# smogbuster-v2.net
KiCad netlist of a schematic drawn in EAGLE
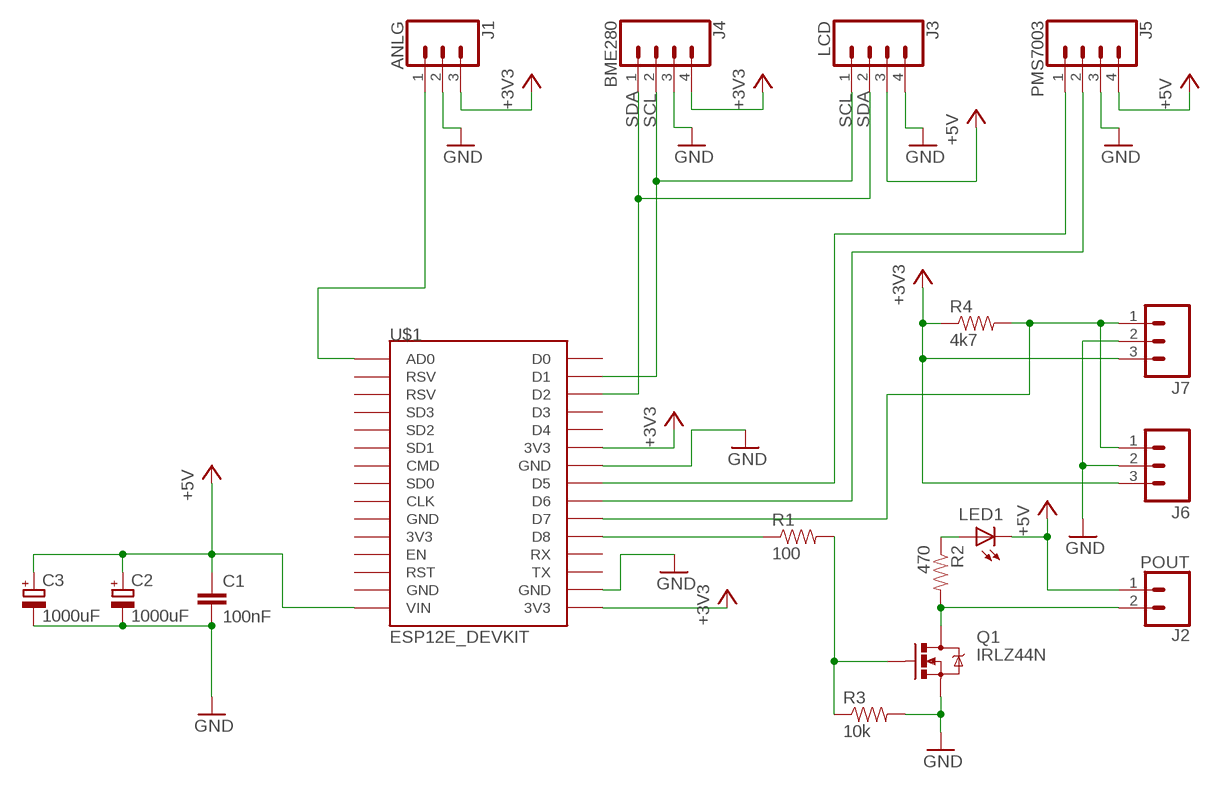
[diagram p0: schematic, sheet 1]

(export (version "E")
  (design (tool "Eeschema 10.0.6"))
  (components
    (comp (ref "C1")
      (value "100nF")
      (footprint "eagle-import:CAP-PTH-5MM")
      (libsource (lib "eagle-import") (part "CAPPTH1"))
    )
    (comp (ref "C2")
      (value "1000uF")
      (footprint "eagle-import:E2,5-7")
      (libsource (lib "eagle-import") (part "CPOL-EUE2.5-7"))
    )
    (comp (ref "C3")
      (value "1000uF")
      (footprint "eagle-import:E2,5-7")
      (libsource (lib "eagle-import") (part "CPOL-EUE2.5-7"))
    )
    (comp (ref "J1")
      (value "ANLG")
      (footprint "eagle-import:1X03")
      (libsource (lib "eagle-import") (part "CONN_03"))
    )
    (comp (ref "J2")
      (value "POUT")
      (footprint "eagle-import:1X02")
      (libsource (lib "eagle-import") (part "CONN_02"))
    )
    (comp (ref "J3")
      (value "LCD")
      (footprint "eagle-import:1X04")
      (libsource (lib "eagle-import") (part "CONN_04"))
    )
    (comp (ref "J4")
      (value "BME280")
      (footprint "eagle-import:1X04")
      (libsource (lib "eagle-import") (part "CONN_04"))
    )
    (comp (ref "J5")
      (value "PMS7003")
      (footprint "eagle-import:1X04")
      (libsource (lib "eagle-import") (part "CONN_04"))
    )
    (comp (ref "J6")
      (value "M03PTH")
      (footprint "eagle-import:1X03")
      (libsource (lib "eagle-import") (part "M03PTH"))
    )
    (comp (ref "J7")
      (value "M03PTH")
      (footprint "eagle-import:1X03")
      (libsource (lib "eagle-import") (part "M03PTH"))
    )
    (comp (ref "LED1")
      (value "LED3MM")
      (footprint "eagle-import:LED3MM")
      (libsource (lib "eagle-import") (part "LED3MM"))
    )
    (comp (ref "Q1")
      (value "IRLZ44N")
      (footprint "eagle-import:TO220V")
      (libsource (lib "eagle-import") (part "MOSFET-NCHANNELFQP30N06L"))
    )
    (comp (ref "R1")
      (value "100")
      (footprint "eagle-import:AXIAL-0.3")
      (libsource (lib "eagle-import") (part "1KOHM-1/4W-1%(PTH)"))
    )
    (comp (ref "R2")
      (value "470")
      (footprint "eagle-import:AXIAL-0.3")
      (libsource (lib "eagle-import") (part "1KOHM-1/4W-1%(PTH)"))
    )
    (comp (ref "R3")
      (value "10k")
      (footprint "eagle-import:AXIAL-0.3")
      (libsource (lib "eagle-import") (part "1KOHM-1/4W-1%(PTH)"))
    )
    (comp (ref "R4")
      (value "4k7")
      (footprint "eagle-import:AXIAL-0.3")
      (libsource (lib "eagle-import") (part "1KOHM-1/4W-1%(PTH)"))
    )
    (comp (ref "U$1")
      (value "ESP12E_DEVKIT")
      (footprint "eagle-import:ESP12E_DEVKIT")
      (fields (field (name "SPICEPREFIX") "X"))
      (libsource (lib "eagle-import") (part "ESP12E_DEVKIT"))
    )
  )
  (nets
    (net (code "1") (name "+3V3") (class "Default")
      (node (ref "J1") (pin "3") (pinfunction "3_3") (pintype "passive"))
      (node (ref "J4") (pin "4") (pinfunction "4_4") (pintype "passive"))
      (node (ref "J6") (pin "3") (pinfunction "3_3") (pintype "passive"))
      (node (ref "J7") (pin "3") (pinfunction "3_3") (pintype "passive"))
      (node (ref "R4") (pin "P$1") (pinfunction "1_P$1") (pintype "passive"))
      (node (ref "U$1") (pin "3V3@1") (pinfunction "3V3_3V3@1") (pintype "bidirectional"))
      (node (ref "U$1") (pin "3V3@2") (pinfunction "3V3_3V3@2") (pintype "bidirectional"))
    )
    (net (code "2") (name "+5V") (class "Default")
      (node (ref "C1") (pin "1") (pinfunction "1_1") (pintype "passive"))
      (node (ref "C2") (pin "+") (pinfunction "+_+") (pintype "passive"))
      (node (ref "C3") (pin "+") (pinfunction "+_+") (pintype "passive"))
      (node (ref "J2") (pin "1") (pinfunction "1_1") (pintype "passive"))
      (node (ref "J3") (pin "3") (pinfunction "3_3") (pintype "passive"))
      (node (ref "J5") (pin "4") (pinfunction "4_4") (pintype "passive"))
      (node (ref "LED1") (pin "K") (pinfunction "C_K") (pintype "passive"))
      (node (ref "U$1") (pin "VIN") (pinfunction "VIN_VIN") (pintype "bidirectional"))
    )
    (net (code "3") (name "/SCL") (class "Default")
      (node (ref "J3") (pin "1") (pinfunction "1_1") (pintype "passive"))
      (node (ref "J4") (pin "2") (pinfunction "2_2") (pintype "passive"))
      (node (ref "U$1") (pin "D1") (pinfunction "D1_D1") (pintype "bidirectional"))
    )
    (net (code "4") (name "/SDA") (class "Default")
      (node (ref "J3") (pin "2") (pinfunction "2_2") (pintype "passive"))
      (node (ref "J4") (pin "1") (pinfunction "1_1") (pintype "passive"))
      (node (ref "U$1") (pin "D2") (pinfunction "D2_D2") (pintype "bidirectional"))
    )
    (net (code "5") (name "GND") (class "Default")
      (node (ref "C1") (pin "2") (pinfunction "2_2") (pintype "passive"))
      (node (ref "C2") (pin "-") (pinfunction "-_-") (pintype "passive"))
      (node (ref "C3") (pin "-") (pinfunction "-_-") (pintype "passive"))
      (node (ref "J1") (pin "2") (pinfunction "2_2") (pintype "passive"))
      (node (ref "J3") (pin "4") (pinfunction "4_4") (pintype "passive"))
      (node (ref "J4") (pin "3") (pinfunction "3_3") (pintype "passive"))
      (node (ref "J5") (pin "3") (pinfunction "3_3") (pintype "passive"))
      (node (ref "J6") (pin "2") (pinfunction "2_2") (pintype "passive"))
      (node (ref "J7") (pin "2") (pinfunction "2_2") (pintype "passive"))
      (node (ref "Q1") (pin "3") (pinfunction "S_3") (pintype "passive"))
      (node (ref "R3") (pin "P$2") (pinfunction "2_P$2") (pintype "passive"))
      (node (ref "U$1") (pin "GND@2") (pinfunction "GND_GND@2") (pintype "bidirectional"))
      (node (ref "U$1") (pin "GND@3") (pinfunction "GND_GND@3") (pintype "bidirectional"))
    )
    (net (code "6") (name "Net-(J1-Pad1)") (class "Default")
      (node (ref "J1") (pin "1") (pinfunction "1_1") (pintype "passive"))
      (node (ref "U$1") (pin "AD0") (pinfunction "AD0_AD0") (pintype "bidirectional"))
    )
    (net (code "7") (name "Net-(J5-Pad1)") (class "Default")
      (node (ref "J5") (pin "1") (pinfunction "1_1") (pintype "passive"))
      (node (ref "U$1") (pin "D5") (pinfunction "D5_D5") (pintype "bidirectional"))
    )
    (net (code "8") (name "Net-(J5-Pad2)") (class "Default")
      (node (ref "J5") (pin "2") (pinfunction "2_2") (pintype "passive"))
      (node (ref "U$1") (pin "D6") (pinfunction "D6_D6") (pintype "bidirectional"))
    )
    (net (code "9") (name "Net-(Q1-D)") (class "Default")
      (node (ref "J2") (pin "2") (pinfunction "2_2") (pintype "passive"))
      (node (ref "Q1") (pin "2") (pinfunction "D_2") (pintype "passive"))
      (node (ref "R2") (pin "P$2") (pinfunction "2_P$2") (pintype "passive"))
    )
    (net (code "10") (name "Net-(Q1-G)") (class "Default")
      (node (ref "Q1") (pin "1") (pinfunction "G_1") (pintype "passive"))
      (node (ref "R1") (pin "P$2") (pinfunction "2_P$2") (pintype "passive"))
      (node (ref "R3") (pin "P$1") (pinfunction "1_P$1") (pintype "passive"))
    )
    (net (code "11") (name "Net-(R1-1)") (class "Default")
      (node (ref "R1") (pin "P$1") (pinfunction "1_P$1") (pintype "passive"))
      (node (ref "U$1") (pin "D8") (pinfunction "D8_D8") (pintype "bidirectional"))
    )
    (net (code "12") (name "Net-(R2-1)") (class "Default")
      (node (ref "LED1") (pin "A") (pinfunction "A_A") (pintype "passive"))
      (node (ref "R2") (pin "P$1") (pinfunction "1_P$1") (pintype "passive"))
    )
    (net (code "13") (name "Net-(R4-2)") (class "Default")
      (node (ref "J6") (pin "1") (pinfunction "1_1") (pintype "passive"))
      (node (ref "J7") (pin "1") (pinfunction "1_1") (pintype "passive"))
      (node (ref "R4") (pin "P$2") (pinfunction "2_P$2") (pintype "passive"))
      (node (ref "U$1") (pin "D7") (pinfunction "D7_D7") (pintype "bidirectional"))
    )
    (net (code "14") (name "unconnected-(U$1-3V3-Pad3V3@0)") (class "Default")
      (node (ref "U$1") (pin "3V3@0") (pinfunction "3V3_3V3@0") (pintype "bidirectional"))
    )
    (net (code "15") (name "unconnected-(U$1-GND-PadGND@0)") (class "Default")
      (node (ref "U$1") (pin "GND@0") (pinfunction "GND_GND@0") (pintype "bidirectional"))
    )
    (net (code "16") (name "unconnected-(U$1-GND-PadGND@1)") (class "Default")
      (node (ref "U$1") (pin "GND@1") (pinfunction "GND_GND@1") (pintype "bidirectional"))
    )
    (net (code "17") (name "unconnected-(U$1-PadCLK)") (class "Default")
      (node (ref "U$1") (pin "CLK") (pinfunction "CLK_CLK") (pintype "bidirectional"))
    )
    (net (code "18") (name "unconnected-(U$1-PadCMD)") (class "Default")
      (node (ref "U$1") (pin "CMD") (pinfunction "CMD_CMD") (pintype "bidirectional"))
    )
    (net (code "19") (name "unconnected-(U$1-PadD0)") (class "Default")
      (node (ref "U$1") (pin "D0") (pinfunction "D0_D0") (pintype "bidirectional"))
    )
    (net (code "20") (name "unconnected-(U$1-PadD3)") (class "Default")
      (node (ref "U$1") (pin "D3") (pinfunction "D3_D3") (pintype "bidirectional"))
    )
    (net (code "21") (name "unconnected-(U$1-PadD4)") (class "Default")
      (node (ref "U$1") (pin "D4") (pinfunction "D4_D4") (pintype "bidirectional"))
    )
    (net (code "22") (name "unconnected-(U$1-PadEN)") (class "Default")
      (node (ref "U$1") (pin "EN") (pinfunction "EN_EN") (pintype "bidirectional"))
    )
    (net (code "23") (name "unconnected-(U$1-PadRST)") (class "Default")
      (node (ref "U$1") (pin "RST") (pinfunction "RST_RST") (pintype "bidirectional"))
    )
    (net (code "24") (name "unconnected-(U$1-PadRX)") (class "Default")
      (node (ref "U$1") (pin "RX") (pinfunction "RX_RX") (pintype "bidirectional"))
    )
    (net (code "25") (name "unconnected-(U$1-PadSD0)") (class "Default")
      (node (ref "U$1") (pin "SD0") (pinfunction "SD0_SD0") (pintype "bidirectional"))
    )
    (net (code "26") (name "unconnected-(U$1-PadSD1)") (class "Default")
      (node (ref "U$1") (pin "SD1") (pinfunction "SD1_SD1") (pintype "bidirectional"))
    )
    (net (code "27") (name "unconnected-(U$1-PadSD2)") (class "Default")
      (node (ref "U$1") (pin "SD2") (pinfunction "SD2_SD2") (pintype "bidirectional"))
    )
    (net (code "28") (name "unconnected-(U$1-PadSD3)") (class "Default")
      (node (ref "U$1") (pin "SD3") (pinfunction "SD3_SD3") (pintype "bidirectional"))
    )
    (net (code "29") (name "unconnected-(U$1-PadTX)") (class "Default")
      (node (ref "U$1") (pin "TX") (pinfunction "TX_TX") (pintype "bidirectional"))
    )
    (net (code "30") (name "unconnected-(U$1-RSV-PadRSV@0)") (class "Default")
      (node (ref "U$1") (pin "RSV@0") (pinfunction "RSV_RSV@0") (pintype "bidirectional"))
    )
    (net (code "31") (name "unconnected-(U$1-RSV-PadRSV@1)") (class "Default")
      (node (ref "U$1") (pin "RSV@1") (pinfunction "RSV_RSV@1") (pintype "bidirectional"))
    )
  )
)
